# Sheet1_Young.net
KiCad netlist of a schematic drawn in Altium Designer
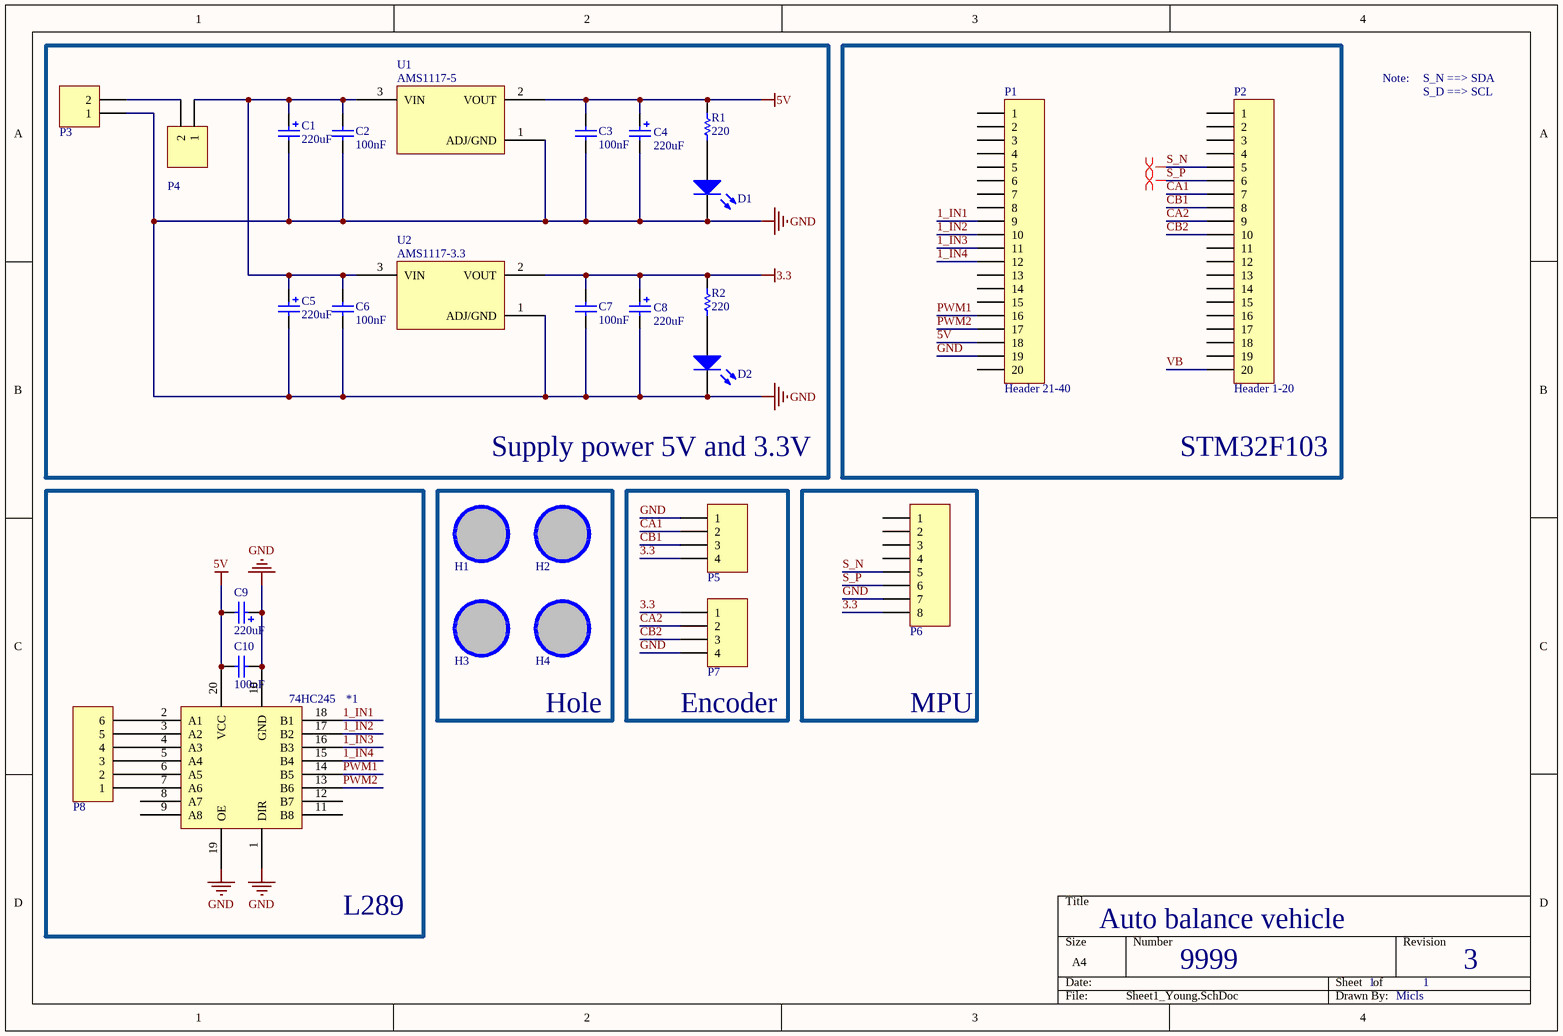
[diagram p0: Sheet1_Young.SchDoc]

(export (version "E")
  (design (tool "Eeschema 10.0.6"))
  (components
    (comp (ref "*1")
      (value "74HC245")
      (footprint "DIP20-3D")
      (libsource (lib "Bus Transceiver") (part "74HC245"))
    )
    (comp (ref "C1")
      (value "220uF")
      (footprint "CAP ALU SIZE B")
      (description "Polarized Capacitor (Radial)")
      (fields (field (name "Comment") "Cap Pol SMD"))
      (libsource (lib "PIF_Library") (part "Cap Pol SMD"))
    )
    (comp (ref "C2")
      (value "100nF")
      (footprint "CAP-SM-0805")
      (description "Capacitor")
      (fields (field (name "Comment") "Cap Non-Pol SMD"))
      (libsource (lib "PIF_Library") (part "Cap Non-Pol SMD"))
    )
    (comp (ref "C3")
      (value "100nF")
      (footprint "CAP-SM-0805")
      (description "Capacitor")
      (fields (field (name "Comment") "Cap Non-Pol SMD"))
      (libsource (lib "PIF_Library") (part "Cap Non-Pol SMD"))
    )
    (comp (ref "C4")
      (value "220uF")
      (footprint "CAP ALU SIZE B")
      (description "Polarized Capacitor (Radial)")
      (fields (field (name "Comment") "Cap Pol SMD"))
      (libsource (lib "PIF_Library") (part "Cap Pol SMD"))
    )
    (comp (ref "C5")
      (value "220uF")
      (footprint "CAP ALU SIZE B")
      (description "Polarized Capacitor (Radial)")
      (fields (field (name "Comment") "Cap Pol SMD"))
      (libsource (lib "PIF_Library") (part "Cap Pol SMD"))
    )
    (comp (ref "C6")
      (value "100nF")
      (footprint "CAP-SM-0805")
      (description "Capacitor")
      (fields (field (name "Comment") "Cap Non-Pol SMD"))
      (libsource (lib "PIF_Library") (part "Cap Non-Pol SMD"))
    )
    (comp (ref "C7")
      (value "100nF")
      (footprint "CAP-SM-0805")
      (description "Capacitor")
      (fields (field (name "Comment") "Cap Non-Pol SMD"))
      (libsource (lib "PIF_Library") (part "Cap Non-Pol SMD"))
    )
    (comp (ref "C8")
      (value "220uF")
      (footprint "CAP ALU SIZE B")
      (description "Polarized Capacitor (Radial)")
      (fields (field (name "Comment") "Cap Pol SMD"))
      (libsource (lib "PIF_Library") (part "Cap Pol SMD"))
    )
    (comp (ref "C9")
      (value "220uF")
      (footprint "CAP ALU SIZE B")
      (description "Polarized Capacitor (Radial)")
      (fields (field (name "Comment") "Cap Pol SMD"))
      (libsource (lib "PIF_Library") (part "Cap Pol SMD"))
    )
    (comp (ref "C10")
      (value "100nF")
      (footprint "CAP-SM-0805")
      (description "Capacitor")
      (fields (field (name "Comment") "Cap Non-Pol SMD"))
      (libsource (lib "PIF_Library") (part "Cap Non-Pol SMD"))
    )
    (comp (ref "D1")
      (value "LED SMD")
      (footprint "LED_0805_Blue")
      (description "LED")
      (libsource (lib "PIF_Library") (part "LED SMD"))
    )
    (comp (ref "D2")
      (value "LED SMD")
      (footprint "LED_0805_Blue")
      (description "LED")
      (libsource (lib "PIF_Library") (part "LED SMD"))
    )
    (comp (ref "H1")
      (value "Hole")
      (footprint "LO KHOAN 3MM")
      (description "Hole 3mm")
      (libsource (lib "PIF_Library") (part "Hole"))
    )
    (comp (ref "H2")
      (value "Hole")
      (footprint "LO KHOAN 3MM")
      (description "Hole 3mm")
      (libsource (lib "PIF_Library") (part "Hole"))
    )
    (comp (ref "H3")
      (value "Hole")
      (footprint "LO KHOAN 3MM")
      (description "Hole 3mm")
      (libsource (lib "PIF_Library") (part "Hole"))
    )
    (comp (ref "H4")
      (value "Hole")
      (footprint "LO KHOAN 3MM")
      (description "Hole 3mm")
      (libsource (lib "PIF_Library") (part "Hole"))
    )
    (comp (ref "P1")
      (value "Header 21-40")
      (footprint "HDR1X20")
      (description "Header, 20-Pin")
      (fields (field (name "PUBLISHER") "Altium Limited"))
      (libsource (lib "Miscellaneous Connectors") (part "Header 20"))
    )
    (comp (ref "P2")
      (value "Header 1-20")
      (footprint "HDR1X20")
      (description "Header, 20-Pin")
      (fields (field (name "PUBLISHER") "Altium Limited"))
      (libsource (lib "Miscellaneous Connectors") (part "Header 20"))
    )
    (comp (ref "P3")
      (value "Domino 2")
      (footprint "DOMINO 2- 5mm")
      (description "Domino, 2-Pin")
      (fields (field (name "PUBLISHER") "Altium Limited"))
      (libsource (lib "PIF_Library") (part "Domino 2"))
    )
    (comp (ref "P4")
      (value "Domino 2")
      (footprint "DOMINO 2- 5mm")
      (description "Domino, 2-Pin")
      (fields (field (name "PUBLISHER") "Altium Limited"))
      (libsource (lib "") (part "Domino 2_1"))
    )
    (comp (ref "P5")
      (value "Header 4")
      (footprint "JP4")
      (description "Header, 4-Pin")
      (fields (field (name "PUBLISHER") "Altium Limited"))
      (libsource (lib "PIF_Library") (part "Header 4"))
    )
    (comp (ref "P6")
      (value "Header 8")
      (footprint "JP8")
      (description "Header, 8-Pin")
      (fields (field (name "PUBLISHER") "Altium Limited"))
      (libsource (lib "PIF_Library") (part "Header 8"))
    )
    (comp (ref "P7")
      (value "Header 4")
      (footprint "JP4")
      (description "Header, 4-Pin")
      (fields (field (name "PUBLISHER") "Altium Limited"))
      (libsource (lib "PIF_Library") (part "Header 4"))
    )
    (comp (ref "P8")
      (value "Header 6")
      (footprint "JP6")
      (description "Header, 6-Pin")
      (fields (field (name "PUBLISHER") "Altium Limited"))
      (libsource (lib "PIF_Library") (part "Header 6"))
    )
    (comp (ref "R1")
      (value "220")
      (footprint "RES-SM-0805")
      (description "Resistor")
      (fields (field (name "Comment") "RESISTOR SMD"))
      (libsource (lib "PIF_Library") (part "RESISTOR SMD"))
    )
    (comp (ref "R2")
      (value "220")
      (footprint "RES-SM-0805")
      (description "Resistor")
      (fields (field (name "Comment") "RESISTOR SMD"))
      (libsource (lib "PIF_Library") (part "RESISTOR SMD"))
    )
    (comp (ref "U1")
      (value "AMS1117-5")
      (footprint "SOT230P700X180-4N")
      (fields (field (name "MP") "AMS1117-3.3") (field (name "MF") "NEC"))
      (libsource (lib "AMS1117-3.3") (part "AMS1117-3.3"))
    )
    (comp (ref "U2")
      (value "AMS1117-3.3")
      (footprint "SOT230P700X180-4N")
      (fields (field (name "MF") "NEC"))
      (libsource (lib "AMS1117-3.3") (part "AMS1117-3.3"))
    )
  )
  (nets
    (net (code "1") (name "/1_IN1") (class "Default")
      (node (ref "*1") (pin "18") (pinfunction "B1_18") (pintype "passive"))
      (node (ref "P1") (pin "9") (pinfunction "9_9") (pintype "passive"))
    )
    (net (code "2") (name "/1_IN2") (class "Default")
      (node (ref "*1") (pin "17") (pinfunction "B2_17") (pintype "passive"))
      (node (ref "P1") (pin "10") (pinfunction "10_10") (pintype "passive"))
    )
    (net (code "3") (name "/1_IN3") (class "Default")
      (node (ref "*1") (pin "16") (pinfunction "B3_16") (pintype "passive"))
      (node (ref "P1") (pin "11") (pinfunction "11_11") (pintype "passive"))
    )
    (net (code "4") (name "/1_IN4") (class "Default")
      (node (ref "*1") (pin "15") (pinfunction "B4_15") (pintype "passive"))
      (node (ref "P1") (pin "12") (pinfunction "12_12") (pintype "passive"))
    )
    (net (code "5") (name "/CA1") (class "Default")
      (node (ref "P2") (pin "7") (pinfunction "7_7") (pintype "passive"))
      (node (ref "P5") (pin "2") (pinfunction "2_2") (pintype "passive"))
    )
    (net (code "6") (name "/CA2") (class "Default")
      (node (ref "P2") (pin "9") (pinfunction "9_9") (pintype "passive"))
      (node (ref "P7") (pin "2") (pinfunction "2_2") (pintype "passive"))
    )
    (net (code "7") (name "/CB1") (class "Default")
      (node (ref "P2") (pin "8") (pinfunction "8_8") (pintype "passive"))
      (node (ref "P5") (pin "3") (pinfunction "3_3") (pintype "passive"))
    )
    (net (code "8") (name "/CB2") (class "Default")
      (node (ref "P2") (pin "10") (pinfunction "10_10") (pintype "passive"))
      (node (ref "P7") (pin "3") (pinfunction "3_3") (pintype "passive"))
    )
    (net (code "9") (name "/PWM1") (class "Default")
      (node (ref "*1") (pin "14") (pinfunction "B5_14") (pintype "passive"))
      (node (ref "P1") (pin "16") (pinfunction "16_16") (pintype "passive"))
    )
    (net (code "10") (name "/PWM2") (class "Default")
      (node (ref "*1") (pin "13") (pinfunction "B6_13") (pintype "passive"))
      (node (ref "P1") (pin "17") (pinfunction "17_17") (pintype "passive"))
    )
    (net (code "11") (name "/S_N") (class "Default")
      (node (ref "P2") (pin "5") (pinfunction "5_5") (pintype "passive"))
      (node (ref "P6") (pin "5") (pinfunction "5_5") (pintype "passive"))
    )
    (net (code "12") (name "/S_P") (class "Default")
      (node (ref "P2") (pin "6") (pinfunction "6_6") (pintype "passive"))
      (node (ref "P6") (pin "6") (pinfunction "6_6") (pintype "passive"))
    )
    (net (code "13") (name "/VB") (class "Default")
      (node (ref "P2") (pin "20") (pinfunction "20_20") (pintype "passive"))
    )
    (net (code "14") (name "3.3") (class "Default")
      (node (ref "C7") (pin "1") (pinfunction "1_1") (pintype "passive"))
      (node (ref "C8") (pin "1") (pinfunction "1_1") (pintype "passive"))
      (node (ref "P5") (pin "4") (pinfunction "4_4") (pintype "passive"))
      (node (ref "P6") (pin "8") (pinfunction "8_8") (pintype "passive"))
      (node (ref "P7") (pin "1") (pinfunction "1_1") (pintype "passive"))
      (node (ref "R2") (pin "2") (pinfunction "2_2") (pintype "passive"))
      (node (ref "U2") (pin "2") (pinfunction "VOUT_2") (pintype "passive"))
    )
    (net (code "15") (name "5V") (class "Default")
      (node (ref "*1") (pin "20") (pinfunction "VCC_20") (pintype "passive"))
      (node (ref "C10") (pin "1") (pinfunction "1_1") (pintype "passive"))
      (node (ref "C3") (pin "1") (pinfunction "1_1") (pintype "passive"))
      (node (ref "C4") (pin "1") (pinfunction "1_1") (pintype "passive"))
      (node (ref "C9") (pin "2") (pinfunction "2_2") (pintype "passive"))
      (node (ref "P1") (pin "18") (pinfunction "18_18") (pintype "passive"))
      (node (ref "R1") (pin "2") (pinfunction "2_2") (pintype "passive"))
      (node (ref "U1") (pin "2") (pinfunction "VOUT_2") (pintype "passive"))
    )
    (net (code "16") (name "GND") (class "Default")
      (node (ref "*1") (pin "1") (pinfunction "DIR_1") (pintype "passive"))
      (node (ref "*1") (pin "10") (pinfunction "GND_10") (pintype "passive"))
      (node (ref "*1") (pin "19") (pinfunction "OE_19") (pintype "passive"))
      (node (ref "C1") (pin "2") (pinfunction "2_2") (pintype "passive"))
      (node (ref "C10") (pin "2") (pinfunction "2_2") (pintype "passive"))
      (node (ref "C2") (pin "1") (pinfunction "1_1") (pintype "passive"))
      (node (ref "C3") (pin "2") (pinfunction "2_2") (pintype "passive"))
      (node (ref "C4") (pin "2") (pinfunction "2_2") (pintype "passive"))
      (node (ref "C5") (pin "2") (pinfunction "2_2") (pintype "passive"))
      (node (ref "C6") (pin "1") (pinfunction "1_1") (pintype "passive"))
      (node (ref "C7") (pin "2") (pinfunction "2_2") (pintype "passive"))
      (node (ref "C8") (pin "2") (pinfunction "2_2") (pintype "passive"))
      (node (ref "C9") (pin "1") (pinfunction "1_1") (pintype "passive"))
      (node (ref "D1") (pin "2") (pinfunction "K_2") (pintype "passive"))
      (node (ref "D2") (pin "2") (pinfunction "K_2") (pintype "passive"))
      (node (ref "P1") (pin "19") (pinfunction "19_19") (pintype "passive"))
      (node (ref "P3") (pin "1") (pinfunction "1_1") (pintype "passive"))
      (node (ref "P5") (pin "1") (pinfunction "1_1") (pintype "passive"))
      (node (ref "P6") (pin "7") (pinfunction "7_7") (pintype "passive"))
      (node (ref "P7") (pin "4") (pinfunction "4_4") (pintype "passive"))
      (node (ref "U1") (pin "1") (pinfunction "ADJ/GND_1") (pintype "passive"))
      (node (ref "U2") (pin "1") (pinfunction "ADJ/GND_1") (pintype "passive"))
    )
    (net (code "17") (name "Net-(*1-A1)") (class "Default")
      (node (ref "*1") (pin "2") (pinfunction "A1_2") (pintype "passive"))
      (node (ref "P8") (pin "6") (pinfunction "6_6") (pintype "passive"))
    )
    (net (code "18") (name "Net-(*1-A2)") (class "Default")
      (node (ref "*1") (pin "3") (pinfunction "A2_3") (pintype "passive"))
      (node (ref "P8") (pin "5") (pinfunction "5_5") (pintype "passive"))
    )
    (net (code "19") (name "Net-(*1-A3)") (class "Default")
      (node (ref "*1") (pin "4") (pinfunction "A3_4") (pintype "passive"))
      (node (ref "P8") (pin "4") (pinfunction "4_4") (pintype "passive"))
    )
    (net (code "20") (name "Net-(*1-A4)") (class "Default")
      (node (ref "*1") (pin "5") (pinfunction "A4_5") (pintype "passive"))
      (node (ref "P8") (pin "3") (pinfunction "3_3") (pintype "passive"))
    )
    (net (code "21") (name "Net-(*1-A5)") (class "Default")
      (node (ref "*1") (pin "6") (pinfunction "A5_6") (pintype "passive"))
      (node (ref "P8") (pin "2") (pinfunction "2_2") (pintype "passive"))
    )
    (net (code "22") (name "Net-(*1-A6)") (class "Default")
      (node (ref "*1") (pin "7") (pinfunction "A6_7") (pintype "passive"))
      (node (ref "P8") (pin "1") (pinfunction "1_1") (pintype "passive"))
    )
    (net (code "23") (name "Net-(D1-A)") (class "Default")
      (node (ref "D1") (pin "1") (pinfunction "A_1") (pintype "passive"))
      (node (ref "R1") (pin "1") (pinfunction "1_1") (pintype "passive"))
    )
    (net (code "24") (name "Net-(D2-A)") (class "Default")
      (node (ref "D2") (pin "1") (pinfunction "A_1") (pintype "passive"))
      (node (ref "R2") (pin "1") (pinfunction "1_1") (pintype "passive"))
    )
    (net (code "25") (name "Net-(P3-Pad2)") (class "Default")
      (node (ref "P3") (pin "2") (pinfunction "2_2") (pintype "passive"))
      (node (ref "P4") (pin "2") (pinfunction "2_2") (pintype "passive"))
    )
    (net (code "26") (name "Net-(U1-VIN)") (class "Default")
      (node (ref "C1") (pin "1") (pinfunction "1_1") (pintype "passive"))
      (node (ref "C2") (pin "2") (pinfunction "2_2") (pintype "passive"))
      (node (ref "C5") (pin "1") (pinfunction "1_1") (pintype "passive"))
      (node (ref "C6") (pin "2") (pinfunction "2_2") (pintype "passive"))
      (node (ref "P4") (pin "1") (pinfunction "1_1") (pintype "passive"))
      (node (ref "U1") (pin "3") (pinfunction "VIN_3") (pintype "passive"))
      (node (ref "U2") (pin "3") (pinfunction "VIN_3") (pintype "passive"))
    )
    (net (code "27") (name "unconnected-(*1-A7-Pad8)") (class "Default")
      (node (ref "*1") (pin "8") (pinfunction "A7_8") (pintype "passive"))
    )
    (net (code "28") (name "unconnected-(*1-A8-Pad9)") (class "Default")
      (node (ref "*1") (pin "9") (pinfunction "A8_9") (pintype "passive"))
    )
    (net (code "29") (name "unconnected-(*1-B7-Pad12)") (class "Default")
      (node (ref "*1") (pin "12") (pinfunction "B7_12") (pintype "passive"))
    )
    (net (code "30") (name "unconnected-(*1-B8-Pad11)") (class "Default")
      (node (ref "*1") (pin "11") (pinfunction "B8_11") (pintype "passive"))
    )
    (net (code "31") (name "unconnected-(H1-Pad1)") (class "Default")
      (node (ref "H1") (pin "1") (pinfunction "1_1") (pintype "passive"))
    )
    (net (code "32") (name "unconnected-(H2-Pad1)") (class "Default")
      (node (ref "H2") (pin "1") (pinfunction "1_1") (pintype "passive"))
    )
    (net (code "33") (name "unconnected-(H3-Pad1)") (class "Default")
      (node (ref "H3") (pin "1") (pinfunction "1_1") (pintype "passive"))
    )
    (net (code "34") (name "unconnected-(H4-Pad1)") (class "Default")
      (node (ref "H4") (pin "1") (pinfunction "1_1") (pintype "passive"))
    )
    (net (code "35") (name "unconnected-(P1-Pad1)") (class "Default")
      (node (ref "P1") (pin "1") (pinfunction "1_1") (pintype "passive"))
    )
    (net (code "36") (name "unconnected-(P1-Pad2)") (class "Default")
      (node (ref "P1") (pin "2") (pinfunction "2_2") (pintype "passive"))
    )
    (net (code "37") (name "unconnected-(P1-Pad3)") (class "Default")
      (node (ref "P1") (pin "3") (pinfunction "3_3") (pintype "passive"))
    )
    (net (code "38") (name "unconnected-(P1-Pad4)") (class "Default")
      (node (ref "P1") (pin "4") (pinfunction "4_4") (pintype "passive"))
    )
    (net (code "39") (name "unconnected-(P1-Pad5)") (class "Default")
      (node (ref "P1") (pin "5") (pinfunction "5_5") (pintype "passive"))
    )
    (net (code "40") (name "unconnected-(P1-Pad6)") (class "Default")
      (node (ref "P1") (pin "6") (pinfunction "6_6") (pintype "passive"))
    )
    (net (code "41") (name "unconnected-(P1-Pad7)") (class "Default")
      (node (ref "P1") (pin "7") (pinfunction "7_7") (pintype "passive"))
    )
    (net (code "42") (name "unconnected-(P1-Pad8)") (class "Default")
      (node (ref "P1") (pin "8") (pinfunction "8_8") (pintype "passive"))
    )
    (net (code "43") (name "unconnected-(P1-Pad13)") (class "Default")
      (node (ref "P1") (pin "13") (pinfunction "13_13") (pintype "passive"))
    )
    (net (code "44") (name "unconnected-(P1-Pad14)") (class "Default")
      (node (ref "P1") (pin "14") (pinfunction "14_14") (pintype "passive"))
    )
    (net (code "45") (name "unconnected-(P1-Pad15)") (class "Default")
      (node (ref "P1") (pin "15") (pinfunction "15_15") (pintype "passive"))
    )
    (net (code "46") (name "unconnected-(P1-Pad20)") (class "Default")
      (node (ref "P1") (pin "20") (pinfunction "20_20") (pintype "passive"))
    )
    (net (code "47") (name "unconnected-(P2-Pad1)") (class "Default")
      (node (ref "P2") (pin "1") (pinfunction "1_1") (pintype "passive"))
    )
    (net (code "48") (name "unconnected-(P2-Pad2)") (class "Default")
      (node (ref "P2") (pin "2") (pinfunction "2_2") (pintype "passive"))
    )
    (net (code "49") (name "unconnected-(P2-Pad3)") (class "Default")
      (node (ref "P2") (pin "3") (pinfunction "3_3") (pintype "passive"))
    )
    (net (code "50") (name "unconnected-(P2-Pad4)") (class "Default")
      (node (ref "P2") (pin "4") (pinfunction "4_4") (pintype "passive"))
    )
    (net (code "51") (name "unconnected-(P2-Pad11)") (class "Default")
      (node (ref "P2") (pin "11") (pinfunction "11_11") (pintype "passive"))
    )
    (net (code "52") (name "unconnected-(P2-Pad12)") (class "Default")
      (node (ref "P2") (pin "12") (pinfunction "12_12") (pintype "passive"))
    )
    (net (code "53") (name "unconnected-(P2-Pad13)") (class "Default")
      (node (ref "P2") (pin "13") (pinfunction "13_13") (pintype "passive"))
    )
    (net (code "54") (name "unconnected-(P2-Pad14)") (class "Default")
      (node (ref "P2") (pin "14") (pinfunction "14_14") (pintype "passive"))
    )
    (net (code "55") (name "unconnected-(P2-Pad15)") (class "Default")
      (node (ref "P2") (pin "15") (pinfunction "15_15") (pintype "passive"))
    )
    (net (code "56") (name "unconnected-(P2-Pad16)") (class "Default")
      (node (ref "P2") (pin "16") (pinfunction "16_16") (pintype "passive"))
    )
    (net (code "57") (name "unconnected-(P2-Pad17)") (class "Default")
      (node (ref "P2") (pin "17") (pinfunction "17_17") (pintype "passive"))
    )
    (net (code "58") (name "unconnected-(P2-Pad18)") (class "Default")
      (node (ref "P2") (pin "18") (pinfunction "18_18") (pintype "passive"))
    )
    (net (code "59") (name "unconnected-(P2-Pad19)") (class "Default")
      (node (ref "P2") (pin "19") (pinfunction "19_19") (pintype "passive"))
    )
    (net (code "60") (name "unconnected-(P6-Pad1)") (class "Default")
      (node (ref "P6") (pin "1") (pinfunction "1_1") (pintype "passive"))
    )
    (net (code "61") (name "unconnected-(P6-Pad2)") (class "Default")
      (node (ref "P6") (pin "2") (pinfunction "2_2") (pintype "passive"))
    )
    (net (code "62") (name "unconnected-(P6-Pad3)") (class "Default")
      (node (ref "P6") (pin "3") (pinfunction "3_3") (pintype "passive"))
    )
    (net (code "63") (name "unconnected-(P6-Pad4)") (class "Default")
      (node (ref "P6") (pin "4") (pinfunction "4_4") (pintype "passive"))
    )
  )
)
